# uC_ATMEL.net
KiCad netlist of a schematic drawn in EAGLE
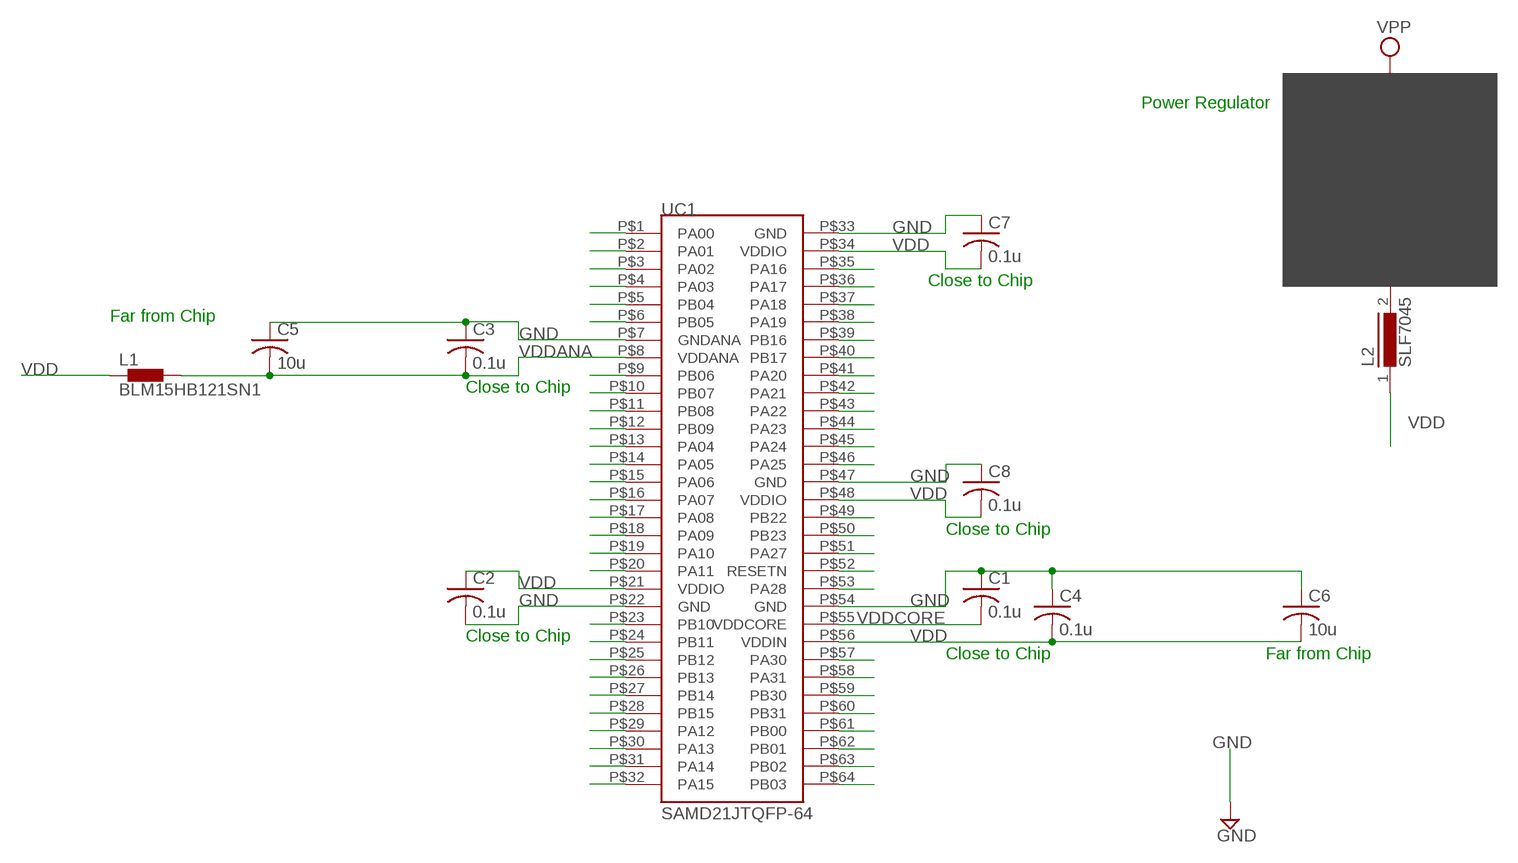
[diagram p0: schematic, sheet 1]
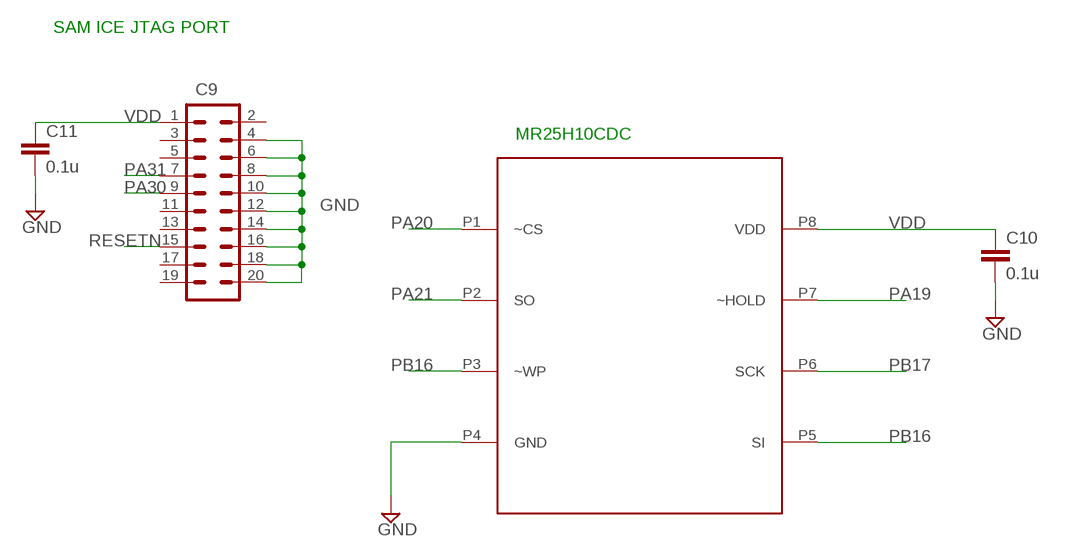
[diagram p1: schematic, sheet 2]
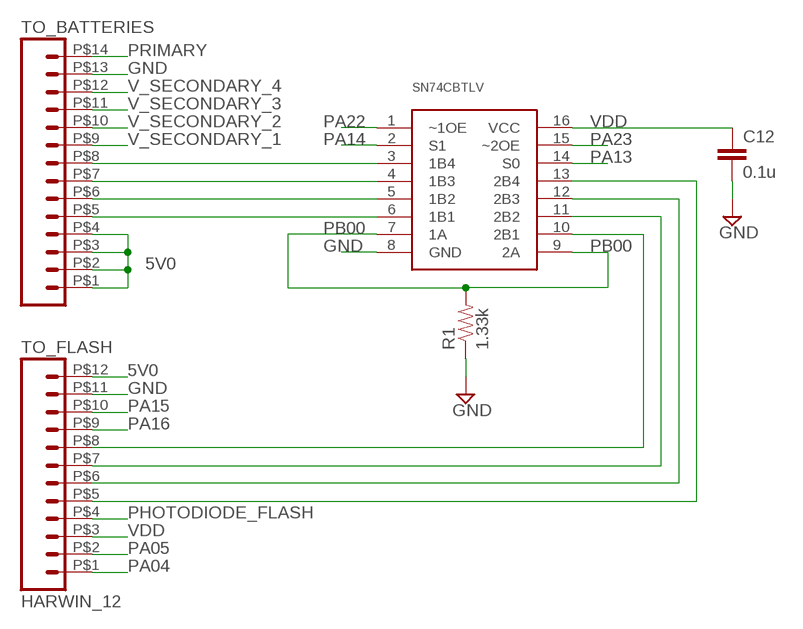
[diagram p2: schematic, sheet 3]
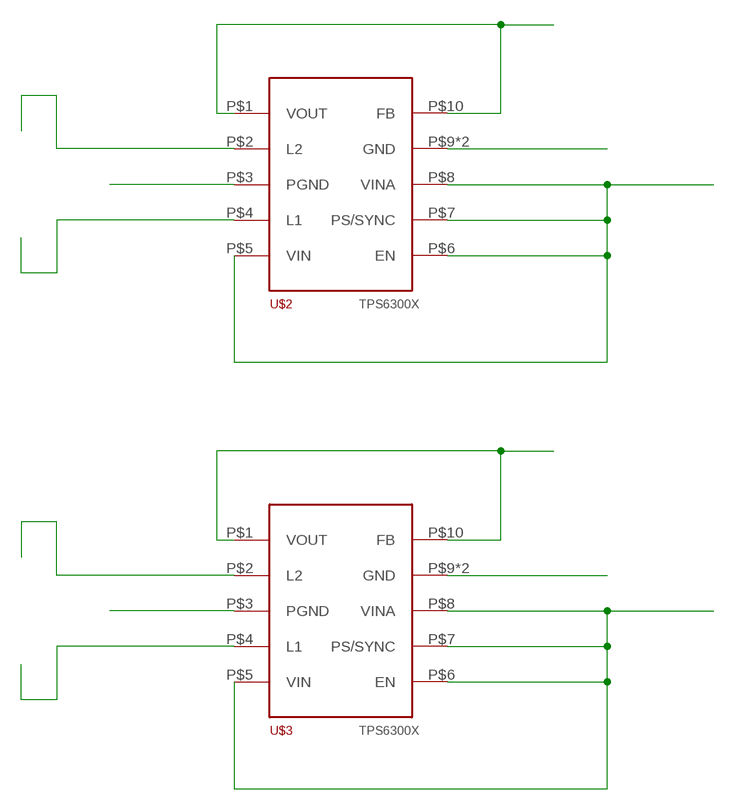
[diagram p3: schematic, sheet 4]
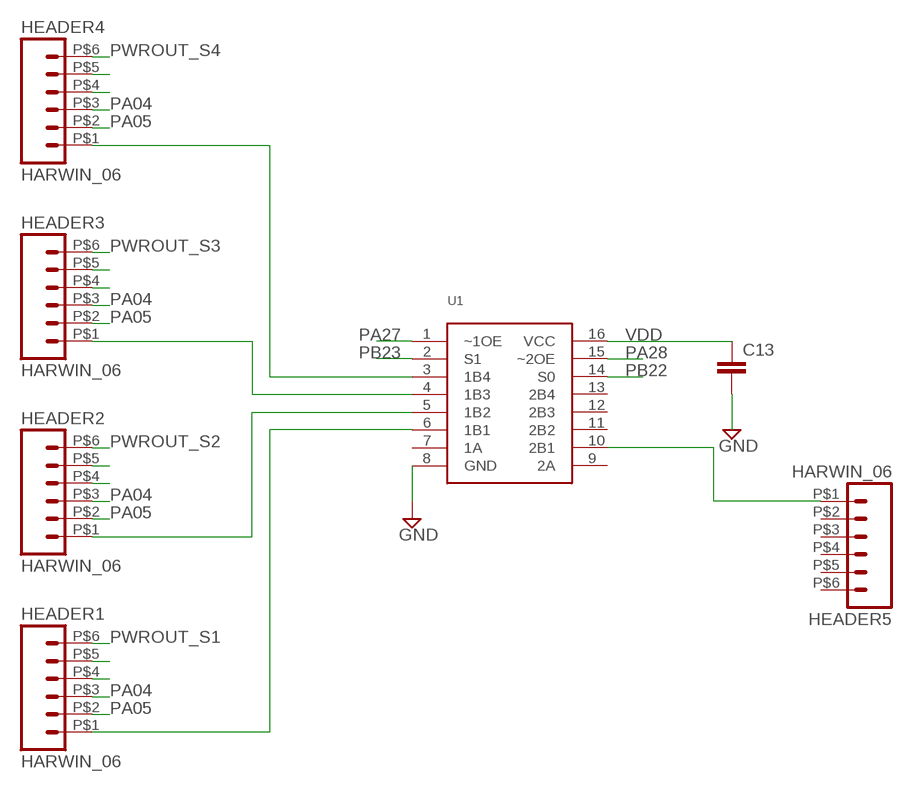
[diagram p4: schematic, sheet 5]

(export (version "E")
  (design (tool "Eeschema 10.0.6"))
  (components
    (comp (ref "C1")
      (value "0.1u")
      (footprint "eagle-import:C1812")
      (libsource (lib "eagle-import") (part "C-USC1812"))
    )
    (comp (ref "C2")
      (value "0.1u")
      (footprint "eagle-import:C1812")
      (libsource (lib "eagle-import") (part "C-USC1812"))
    )
    (comp (ref "C3")
      (value "0.1u")
      (footprint "eagle-import:C1812")
      (libsource (lib "eagle-import") (part "C-USC1812"))
    )
    (comp (ref "C4")
      (value "0.1u")
      (footprint "eagle-import:C1812")
      (libsource (lib "eagle-import") (part "C-USC1812"))
    )
    (comp (ref "C5")
      (value "10u")
      (footprint "eagle-import:C1206")
      (libsource (lib "eagle-import") (part "C-USC1206"))
    )
    (comp (ref "C6")
      (value "10u")
      (footprint "eagle-import:C1206")
      (libsource (lib "eagle-import") (part "C-USC1206"))
    )
    (comp (ref "C7")
      (value "0.1u")
      (footprint "eagle-import:C1812")
      (libsource (lib "eagle-import") (part "C-USC1812"))
    )
    (comp (ref "C8")
      (value "0.1u")
      (footprint "eagle-import:C1812")
      (libsource (lib "eagle-import") (part "C-USC1812"))
    )
    (comp (ref "L1")
      (value "BLM15HB121SN1")
      (footprint "eagle-import:0402")
      (libsource (lib "eagle-import") (part "BLM15HB121SN1"))
    )
    (comp (ref "L2")
      (value "SLF7045")
      (footprint "eagle-import:SLF7045")
      (libsource (lib "eagle-import") (part "SLF7045"))
    )
    (comp (ref "UC1")
      (value "SAMD21JTQFP-64")
      (footprint "eagle-import:TQFP-64")
      (libsource (lib "eagle-import") (part "SAMD21JTQFP-64"))
    )
    (comp (ref "C12")
      (value "0.1u")
      (footprint "eagle-import:0805")
      (libsource (lib "eagle-import") (part "CAP0805"))
    )
    (comp (ref "R1")
      (value "1.33k")
      (footprint "eagle-import:0805")
      (libsource (lib "eagle-import") (part "RESISTOR"))
    )
    (comp (ref "SN74CBTLV")
      (value "SN74CBTLV3253")
      (footprint "eagle-import:SOIC16R")
      (libsource (lib "eagle-import") (part "SN74CBTLV3253"))
    )
    (comp (ref "TO_BATTERIES")
      (value "HARWIN_14")
      (footprint "eagle-import:HARWIN_DATAMATE_14")
      (libsource (lib "eagle-import") (part "HARWIN_14"))
    )
    (comp (ref "TO_FLASH")
      (value "HARWIN_12")
      (footprint "eagle-import:HARWIN_DATAMATE_12")
      (libsource (lib "eagle-import") (part "HARWIN_12"))
    )
    (comp (ref "U$2")
      (value "TPS6300X")
      (footprint "eagle-import:QFN10_POWERPAD")
      (libsource (lib "eagle-import") (part "TPS6300X"))
    )
    (comp (ref "U$3")
      (value "TPS6300X")
      (footprint "eagle-import:QFN10_POWERPAD")
      (libsource (lib "eagle-import") (part "TPS6300X"))
    )
    (comp (ref "C9")
      (value "IDC_JTAG_CONNECTOR")
      (footprint "eagle-import:2X10")
      (libsource (lib "eagle-import") (part "IDC_JTAG_CONNECTOR"))
    )
    (comp (ref "C10")
      (value "0.1u")
      (footprint "eagle-import:0805")
      (libsource (lib "eagle-import") (part "CAP0805"))
    )
    (comp (ref "C11")
      (value "0.1u")
      (footprint "eagle-import:0805")
      (libsource (lib "eagle-import") (part "CAP0805"))
    )
    (comp (ref "U$1")
      (value "MR25H10CDC")
      (footprint "eagle-import:8PXMO-229")
      (libsource (lib "eagle-import") (part "MR25H10CDC"))
    )
    (comp (ref "C13")
      (value "CAP0805")
      (footprint "eagle-import:0805")
      (libsource (lib "eagle-import") (part "CAP0805"))
    )
    (comp (ref "HEADER1")
      (value "HARWIN_06")
      (footprint "eagle-import:HARWIN_DATAMATE_6")
      (libsource (lib "eagle-import") (part "HARWIN_06"))
    )
    (comp (ref "HEADER2")
      (value "HARWIN_06")
      (footprint "eagle-import:HARWIN_DATAMATE_6")
      (libsource (lib "eagle-import") (part "HARWIN_06"))
    )
    (comp (ref "HEADER3")
      (value "HARWIN_06")
      (footprint "eagle-import:HARWIN_DATAMATE_6")
      (libsource (lib "eagle-import") (part "HARWIN_06"))
    )
    (comp (ref "HEADER4")
      (value "HARWIN_06")
      (footprint "eagle-import:HARWIN_DATAMATE_6")
      (libsource (lib "eagle-import") (part "HARWIN_06"))
    )
    (comp (ref "HEADER5")
      (value "HARWIN_06")
      (footprint "eagle-import:HARWIN_DATAMATE_6")
      (libsource (lib "eagle-import") (part "HARWIN_06"))
    )
    (comp (ref "U1")
      (value "SN74CBTLV3253")
      (footprint "eagle-import:SOIC16R")
      (libsource (lib "eagle-import") (part "SN74CBTLV3253"))
    )
  )
  (nets
    (net (code "1") (name "5V0") (class "Default")
      (node (ref "TO_BATTERIES") (pin "P$1") (pinfunction "1_P$1") (pintype "passive"))
      (node (ref "TO_BATTERIES") (pin "P$2") (pinfunction "2_P$2") (pintype "passive"))
      (node (ref "TO_BATTERIES") (pin "P$3") (pinfunction "3_P$3") (pintype "passive"))
      (node (ref "TO_BATTERIES") (pin "P$4") (pinfunction "4_P$4") (pintype "passive"))
      (node (ref "TO_FLASH") (pin "P$12") (pinfunction "12_P$12") (pintype "passive"))
    )
    (net (code "2") (name "GND") (class "Default")
      (node (ref "C1") (pin "1") (pinfunction "1_1") (pintype "passive"))
      (node (ref "C10") (pin "2") (pinfunction "2_2") (pintype "passive"))
      (node (ref "C11") (pin "2") (pinfunction "2_2") (pintype "passive"))
      (node (ref "C12") (pin "2") (pinfunction "2_2") (pintype "passive"))
      (node (ref "C2") (pin "2") (pinfunction "2_2") (pintype "passive"))
      (node (ref "C3") (pin "1") (pinfunction "1_1") (pintype "passive"))
      (node (ref "C4") (pin "1") (pinfunction "1_1") (pintype "passive"))
      (node (ref "C5") (pin "1") (pinfunction "1_1") (pintype "passive"))
      (node (ref "C6") (pin "1") (pinfunction "1_1") (pintype "passive"))
      (node (ref "C7") (pin "1") (pinfunction "1_1") (pintype "passive"))
      (node (ref "C8") (pin "1") (pinfunction "1_1") (pintype "passive"))
      (node (ref "C9") (pin "10") (pinfunction "10_10") (pintype "passive"))
      (node (ref "C9") (pin "12") (pinfunction "12_12") (pintype "passive"))
      (node (ref "C9") (pin "14") (pinfunction "14_14") (pintype "passive"))
      (node (ref "C9") (pin "16") (pinfunction "16_16") (pintype "passive"))
      (node (ref "C9") (pin "18") (pinfunction "18_18") (pintype "passive"))
      (node (ref "C9") (pin "20") (pinfunction "20_20") (pintype "passive"))
      (node (ref "C9") (pin "4") (pinfunction "4_4") (pintype "passive"))
      (node (ref "C9") (pin "6") (pinfunction "6_6") (pintype "passive"))
      (node (ref "C9") (pin "8") (pinfunction "8_8") (pintype "passive"))
      (node (ref "R1") (pin "1") (pinfunction "1_1") (pintype "passive"))
      (node (ref "SN74CBTLV") (pin "8") (pinfunction "GND_8") (pintype "bidirectional"))
      (node (ref "TO_BATTERIES") (pin "P$13") (pinfunction "13_P$13") (pintype "passive"))
      (node (ref "TO_FLASH") (pin "P$11") (pinfunction "11_P$11") (pintype "passive"))
      (node (ref "U$1") (pin "P4") (pinfunction "GND_P4") (pintype "bidirectional"))
      (node (ref "U1") (pin "8") (pinfunction "GND_8") (pintype "bidirectional"))
      (node (ref "UC1") (pin "P$22") (pinfunction "GND_P$22") (pintype "power_in"))
      (node (ref "UC1") (pin "P$33") (pinfunction "GND_P$33") (pintype "power_in"))
      (node (ref "UC1") (pin "P$47") (pinfunction "GND_P$47") (pintype "power_in"))
      (node (ref "UC1") (pin "P$54") (pinfunction "GND_P$54") (pintype "power_in"))
      (node (ref "UC1") (pin "P$7") (pinfunction "GNDANA_P$7") (pintype "power_in"))
    )
    (net (code "3") (name "Net-(HEADER1-1)") (class "Default")
      (node (ref "HEADER1") (pin "P$1") (pinfunction "1_P$1") (pintype "passive"))
      (node (ref "U1") (pin "6") (pinfunction "1B1_6") (pintype "bidirectional"))
    )
    (net (code "4") (name "Net-(HEADER2-1)") (class "Default")
      (node (ref "HEADER2") (pin "P$1") (pinfunction "1_P$1") (pintype "passive"))
      (node (ref "U1") (pin "5") (pinfunction "1B2_5") (pintype "bidirectional"))
    )
    (net (code "5") (name "Net-(HEADER3-1)") (class "Default")
      (node (ref "HEADER3") (pin "P$1") (pinfunction "1_P$1") (pintype "passive"))
      (node (ref "U1") (pin "4") (pinfunction "1B3_4") (pintype "bidirectional"))
    )
    (net (code "6") (name "Net-(HEADER4-1)") (class "Default")
      (node (ref "HEADER4") (pin "P$1") (pinfunction "1_P$1") (pintype "passive"))
      (node (ref "U1") (pin "3") (pinfunction "1B4_3") (pintype "bidirectional"))
    )
    (net (code "7") (name "Net-(HEADER5-1)") (class "Default")
      (node (ref "HEADER5") (pin "P$1") (pinfunction "1_P$1") (pintype "passive"))
      (node (ref "U1") (pin "10") (pinfunction "2B1_10") (pintype "bidirectional"))
    )
    (net (code "8") (name "Net-(SN74CBTLV-1B1)") (class "Default")
      (node (ref "SN74CBTLV") (pin "6") (pinfunction "1B1_6") (pintype "bidirectional"))
      (node (ref "TO_BATTERIES") (pin "P$5") (pinfunction "5_P$5") (pintype "passive"))
    )
    (net (code "9") (name "Net-(SN74CBTLV-1B2)") (class "Default")
      (node (ref "SN74CBTLV") (pin "5") (pinfunction "1B2_5") (pintype "bidirectional"))
      (node (ref "TO_BATTERIES") (pin "P$6") (pinfunction "6_P$6") (pintype "passive"))
    )
    (net (code "10") (name "Net-(SN74CBTLV-1B3)") (class "Default")
      (node (ref "SN74CBTLV") (pin "4") (pinfunction "1B3_4") (pintype "bidirectional"))
      (node (ref "TO_BATTERIES") (pin "P$7") (pinfunction "7_P$7") (pintype "passive"))
    )
    (net (code "11") (name "Net-(SN74CBTLV-1B4)") (class "Default")
      (node (ref "SN74CBTLV") (pin "3") (pinfunction "1B4_3") (pintype "bidirectional"))
      (node (ref "TO_BATTERIES") (pin "P$8") (pinfunction "8_P$8") (pintype "passive"))
    )
    (net (code "12") (name "Net-(SN74CBTLV-2B1)") (class "Default")
      (node (ref "SN74CBTLV") (pin "10") (pinfunction "2B1_10") (pintype "bidirectional"))
      (node (ref "TO_FLASH") (pin "P$8") (pinfunction "8_P$8") (pintype "passive"))
    )
    (net (code "13") (name "Net-(SN74CBTLV-2B2)") (class "Default")
      (node (ref "SN74CBTLV") (pin "11") (pinfunction "2B2_11") (pintype "bidirectional"))
      (node (ref "TO_FLASH") (pin "P$7") (pinfunction "7_P$7") (pintype "passive"))
    )
    (net (code "14") (name "Net-(SN74CBTLV-2B3)") (class "Default")
      (node (ref "SN74CBTLV") (pin "12") (pinfunction "2B3_12") (pintype "bidirectional"))
      (node (ref "TO_FLASH") (pin "P$6") (pinfunction "6_P$6") (pintype "passive"))
    )
    (net (code "15") (name "Net-(SN74CBTLV-2B4)") (class "Default")
      (node (ref "SN74CBTLV") (pin "13") (pinfunction "2B4_13") (pintype "bidirectional"))
      (node (ref "TO_FLASH") (pin "P$5") (pinfunction "5_P$5") (pintype "passive"))
    )
    (net (code "16") (name "Net-(U$2-EN)") (class "Default")
      (node (ref "U$2") (pin "P$5") (pinfunction "VIN_P$5") (pintype "input"))
      (node (ref "U$2") (pin "P$6") (pinfunction "EN_P$6") (pintype "input"))
      (node (ref "U$2") (pin "P$7") (pinfunction "PS/SYNC_P$7") (pintype "input"))
      (node (ref "U$2") (pin "P$8") (pinfunction "VINA_P$8") (pintype "input"))
    )
    (net (code "17") (name "Net-(U$2-FB)") (class "Default")
      (node (ref "U$2") (pin "P$1") (pinfunction "VOUT_P$1") (pintype "output"))
      (node (ref "U$2") (pin "P$10") (pinfunction "FB_P$10") (pintype "input"))
    )
    (net (code "18") (name "Net-(U$2-GND-PadP$9)") (class "Default")
      (node (ref "U$2") (pin "P$9") (pinfunction "GND_P$9") (pintype "input"))
      (node (ref "U$2") (pin "PAD") (pinfunction "GND_PAD") (pintype "input"))
    )
    (net (code "19") (name "Net-(U$3-EN)") (class "Default")
      (node (ref "U$3") (pin "P$5") (pinfunction "VIN_P$5") (pintype "input"))
      (node (ref "U$3") (pin "P$6") (pinfunction "EN_P$6") (pintype "input"))
      (node (ref "U$3") (pin "P$7") (pinfunction "PS/SYNC_P$7") (pintype "input"))
      (node (ref "U$3") (pin "P$8") (pinfunction "VINA_P$8") (pintype "input"))
    )
    (net (code "20") (name "Net-(U$3-FB)") (class "Default")
      (node (ref "U$3") (pin "P$1") (pinfunction "VOUT_P$1") (pintype "output"))
      (node (ref "U$3") (pin "P$10") (pinfunction "FB_P$10") (pintype "input"))
    )
    (net (code "21") (name "Net-(U$3-GND-PadP$9)") (class "Default")
      (node (ref "U$3") (pin "P$9") (pinfunction "GND_P$9") (pintype "input"))
      (node (ref "U$3") (pin "PAD") (pinfunction "GND_PAD") (pintype "input"))
    )
    (net (code "22") (name "PA04") (class "Default")
      (node (ref "HEADER1") (pin "P$3") (pinfunction "3_P$3") (pintype "passive"))
      (node (ref "HEADER2") (pin "P$3") (pinfunction "3_P$3") (pintype "passive"))
      (node (ref "HEADER3") (pin "P$3") (pinfunction "3_P$3") (pintype "passive"))
      (node (ref "HEADER4") (pin "P$3") (pinfunction "3_P$3") (pintype "passive"))
      (node (ref "TO_FLASH") (pin "P$1") (pinfunction "1_P$1") (pintype "passive"))
      (node (ref "UC1") (pin "P$13") (pinfunction "PA04_P$13") (pintype "bidirectional"))
    )
    (net (code "23") (name "PA05") (class "Default")
      (node (ref "HEADER1") (pin "P$2") (pinfunction "2_P$2") (pintype "passive"))
      (node (ref "HEADER2") (pin "P$2") (pinfunction "2_P$2") (pintype "passive"))
      (node (ref "HEADER3") (pin "P$2") (pinfunction "2_P$2") (pintype "passive"))
      (node (ref "HEADER4") (pin "P$2") (pinfunction "2_P$2") (pintype "passive"))
      (node (ref "TO_FLASH") (pin "P$2") (pinfunction "2_P$2") (pintype "passive"))
      (node (ref "UC1") (pin "P$14") (pinfunction "PA05_P$14") (pintype "bidirectional"))
    )
    (net (code "24") (name "PA13") (class "Default")
      (node (ref "SN74CBTLV") (pin "14") (pinfunction "S0_14") (pintype "bidirectional"))
      (node (ref "UC1") (pin "P$30") (pinfunction "PA13_P$30") (pintype "bidirectional"))
    )
    (net (code "25") (name "PA14") (class "Default")
      (node (ref "SN74CBTLV") (pin "2") (pinfunction "S1_2") (pintype "bidirectional"))
      (node (ref "UC1") (pin "P$31") (pinfunction "PA14_P$31") (pintype "bidirectional"))
    )
    (net (code "26") (name "PA15") (class "Default")
      (node (ref "TO_FLASH") (pin "P$10") (pinfunction "10_P$10") (pintype "passive"))
      (node (ref "UC1") (pin "P$32") (pinfunction "PA15_P$32") (pintype "bidirectional"))
    )
    (net (code "27") (name "PA16") (class "Default")
      (node (ref "TO_FLASH") (pin "P$9") (pinfunction "9_P$9") (pintype "passive"))
      (node (ref "UC1") (pin "P$35") (pinfunction "PA16_P$35") (pintype "bidirectional"))
    )
    (net (code "28") (name "PA19") (class "Default")
      (node (ref "U$1") (pin "P7") (pinfunction "~{HOLD}_P7") (pintype "bidirectional"))
      (node (ref "UC1") (pin "P$38") (pinfunction "PA19_P$38") (pintype "bidirectional"))
    )
    (net (code "29") (name "PA20") (class "Default")
      (node (ref "U$1") (pin "P1") (pinfunction "~{CS}_P1") (pintype "bidirectional"))
      (node (ref "UC1") (pin "P$41") (pinfunction "PA20_P$41") (pintype "bidirectional"))
    )
    (net (code "30") (name "PA21") (class "Default")
      (node (ref "U$1") (pin "P2") (pinfunction "SO_P2") (pintype "bidirectional"))
      (node (ref "UC1") (pin "P$42") (pinfunction "PA21_P$42") (pintype "bidirectional"))
    )
    (net (code "31") (name "PA22") (class "Default")
      (node (ref "SN74CBTLV") (pin "1") (pinfunction "~{1OE}_1") (pintype "bidirectional"))
      (node (ref "UC1") (pin "P$43") (pinfunction "PA22_P$43") (pintype "bidirectional"))
    )
    (net (code "32") (name "PA23") (class "Default")
      (node (ref "SN74CBTLV") (pin "15") (pinfunction "~{2OE}_15") (pintype "bidirectional"))
      (node (ref "UC1") (pin "P$44") (pinfunction "PA23_P$44") (pintype "bidirectional"))
    )
    (net (code "33") (name "PA27") (class "Default")
      (node (ref "U1") (pin "1") (pinfunction "~{1OE}_1") (pintype "bidirectional"))
      (node (ref "UC1") (pin "P$51") (pinfunction "PA27_P$51") (pintype "bidirectional"))
    )
    (net (code "34") (name "PA28") (class "Default")
      (node (ref "U1") (pin "15") (pinfunction "~{2OE}_15") (pintype "bidirectional"))
      (node (ref "UC1") (pin "P$53") (pinfunction "PA28_P$53") (pintype "bidirectional"))
    )
    (net (code "35") (name "PA30") (class "Default")
      (node (ref "C9") (pin "9") (pinfunction "9_9") (pintype "passive"))
      (node (ref "UC1") (pin "P$57") (pinfunction "PA30_P$57") (pintype "bidirectional"))
    )
    (net (code "36") (name "PA31") (class "Default")
      (node (ref "C9") (pin "7") (pinfunction "7_7") (pintype "passive"))
      (node (ref "UC1") (pin "P$58") (pinfunction "PA31_P$58") (pintype "bidirectional"))
    )
    (net (code "37") (name "PB00") (class "Default")
      (node (ref "R1") (pin "2") (pinfunction "2_2") (pintype "passive"))
      (node (ref "SN74CBTLV") (pin "7") (pinfunction "1A_7") (pintype "bidirectional"))
      (node (ref "SN74CBTLV") (pin "9") (pinfunction "2A_9") (pintype "bidirectional"))
      (node (ref "UC1") (pin "P$61") (pinfunction "PB00_P$61") (pintype "bidirectional"))
    )
    (net (code "38") (name "PB16") (class "Default")
      (node (ref "U$1") (pin "P3") (pinfunction "~{WP}_P3") (pintype "bidirectional"))
      (node (ref "U$1") (pin "P5") (pinfunction "SI_P5") (pintype "bidirectional"))
      (node (ref "UC1") (pin "P$39") (pinfunction "PB16_P$39") (pintype "bidirectional"))
    )
    (net (code "39") (name "PB17") (class "Default")
      (node (ref "U$1") (pin "P6") (pinfunction "SCK_P6") (pintype "bidirectional"))
      (node (ref "UC1") (pin "P$40") (pinfunction "PB17_P$40") (pintype "bidirectional"))
    )
    (net (code "40") (name "PB22") (class "Default")
      (node (ref "U1") (pin "14") (pinfunction "S0_14") (pintype "bidirectional"))
      (node (ref "UC1") (pin "P$49") (pinfunction "PB22_P$49") (pintype "bidirectional"))
    )
    (net (code "41") (name "PB23") (class "Default")
      (node (ref "U1") (pin "2") (pinfunction "S1_2") (pintype "bidirectional"))
      (node (ref "UC1") (pin "P$50") (pinfunction "PB23_P$50") (pintype "bidirectional"))
    )
    (net (code "42") (name "PHOTODIODE_FLASH") (class "Default")
      (node (ref "TO_FLASH") (pin "P$4") (pinfunction "4_P$4") (pintype "passive"))
    )
    (net (code "43") (name "PRIMARY") (class "Default")
      (node (ref "TO_BATTERIES") (pin "P$14") (pinfunction "14_P$14") (pintype "passive"))
    )
    (net (code "44") (name "PWROUT_S1") (class "Default")
      (node (ref "HEADER1") (pin "P$6") (pinfunction "6_P$6") (pintype "passive"))
    )
    (net (code "45") (name "PWROUT_S2") (class "Default")
      (node (ref "HEADER2") (pin "P$6") (pinfunction "6_P$6") (pintype "passive"))
    )
    (net (code "46") (name "PWROUT_S3") (class "Default")
      (node (ref "HEADER3") (pin "P$6") (pinfunction "6_P$6") (pintype "passive"))
    )
    (net (code "47") (name "PWROUT_S4") (class "Default")
      (node (ref "HEADER4") (pin "P$6") (pinfunction "6_P$6") (pintype "passive"))
    )
    (net (code "48") (name "RESETN") (class "Default")
      (node (ref "C9") (pin "15") (pinfunction "15_15") (pintype "passive"))
      (node (ref "UC1") (pin "P$52") (pinfunction "RESETN_P$52") (pintype "input"))
    )
    (net (code "49") (name "VDD") (class "Default")
      (node (ref "C10") (pin "1") (pinfunction "1_1") (pintype "passive"))
      (node (ref "C11") (pin "1") (pinfunction "1_1") (pintype "passive"))
      (node (ref "C12") (pin "1") (pinfunction "1_1") (pintype "passive"))
      (node (ref "C13") (pin "1") (pinfunction "1_1") (pintype "passive"))
      (node (ref "C2") (pin "1") (pinfunction "1_1") (pintype "passive"))
      (node (ref "C4") (pin "2") (pinfunction "2_2") (pintype "passive"))
      (node (ref "C6") (pin "2") (pinfunction "2_2") (pintype "passive"))
      (node (ref "C7") (pin "2") (pinfunction "2_2") (pintype "passive"))
      (node (ref "C8") (pin "2") (pinfunction "2_2") (pintype "passive"))
      (node (ref "C9") (pin "1") (pinfunction "1_1") (pintype "passive"))
      (node (ref "L1") (pin "1") (pinfunction "1_1") (pintype "passive"))
      (node (ref "L2") (pin "1") (pinfunction "1_1") (pintype "passive"))
      (node (ref "SN74CBTLV") (pin "16") (pinfunction "VCC_16") (pintype "bidirectional"))
      (node (ref "TO_FLASH") (pin "P$3") (pinfunction "3_P$3") (pintype "passive"))
      (node (ref "U$1") (pin "P8") (pinfunction "VDD_P8") (pintype "bidirectional"))
      (node (ref "U1") (pin "16") (pinfunction "VCC_16") (pintype "bidirectional"))
      (node (ref "UC1") (pin "P$21") (pinfunction "VDDIO_P$21") (pintype "power_in"))
      (node (ref "UC1") (pin "P$34") (pinfunction "VDDIO_P$34") (pintype "power_in"))
      (node (ref "UC1") (pin "P$48") (pinfunction "VDDIO_P$48") (pintype "power_in"))
      (node (ref "UC1") (pin "P$56") (pinfunction "VDDIN_P$56") (pintype "power_in"))
    )
    (net (code "50") (name "VDDANA") (class "Default")
      (node (ref "C3") (pin "2") (pinfunction "2_2") (pintype "passive"))
      (node (ref "C5") (pin "2") (pinfunction "2_2") (pintype "passive"))
      (node (ref "L1") (pin "2") (pinfunction "2_2") (pintype "passive"))
      (node (ref "UC1") (pin "P$8") (pinfunction "VDDANA_P$8") (pintype "power_in"))
    )
    (net (code "51") (name "VDDCORE") (class "Default")
      (node (ref "C1") (pin "2") (pinfunction "2_2") (pintype "passive"))
      (node (ref "UC1") (pin "P$55") (pinfunction "VDDCORE_P$55") (pintype "power_in"))
    )
    (net (code "53") (name "V_SECONDARY_1") (class "Default")
      (node (ref "TO_BATTERIES") (pin "P$9") (pinfunction "9_P$9") (pintype "passive"))
    )
    (net (code "54") (name "V_SECONDARY_2") (class "Default")
      (node (ref "TO_BATTERIES") (pin "P$10") (pinfunction "10_P$10") (pintype "passive"))
    )
    (net (code "55") (name "V_SECONDARY_3") (class "Default")
      (node (ref "TO_BATTERIES") (pin "P$11") (pinfunction "11_P$11") (pintype "passive"))
    )
    (net (code "56") (name "V_SECONDARY_4") (class "Default")
      (node (ref "TO_BATTERIES") (pin "P$12") (pinfunction "12_P$12") (pintype "passive"))
    )
    (net (code "57") (name "unconnected-(C9-Pad2)") (class "Default")
      (node (ref "C9") (pin "2") (pinfunction "2_2") (pintype "passive"))
    )
    (net (code "58") (name "unconnected-(C9-Pad3)") (class "Default")
      (node (ref "C9") (pin "3") (pinfunction "3_3") (pintype "passive"))
    )
    (net (code "59") (name "unconnected-(C9-Pad5)") (class "Default")
      (node (ref "C9") (pin "5") (pinfunction "5_5") (pintype "passive"))
    )
    (net (code "60") (name "unconnected-(C9-Pad11)") (class "Default")
      (node (ref "C9") (pin "11") (pinfunction "11_11") (pintype "passive"))
    )
    (net (code "61") (name "unconnected-(C9-Pad13)") (class "Default")
      (node (ref "C9") (pin "13") (pinfunction "13_13") (pintype "passive"))
    )
    (net (code "62") (name "unconnected-(C9-Pad17)") (class "Default")
      (node (ref "C9") (pin "17") (pinfunction "17_17") (pintype "passive"))
    )
    (net (code "63") (name "unconnected-(C9-Pad19)") (class "Default")
      (node (ref "C9") (pin "19") (pinfunction "19_19") (pintype "passive"))
    )
    (net (code "64") (name "unconnected-(C13-Pad2)") (class "Default")
      (node (ref "C13") (pin "2") (pinfunction "2_2") (pintype "passive"))
    )
    (net (code "65") (name "unconnected-(HEADER1-4-PadP$4)") (class "Default")
      (node (ref "HEADER1") (pin "P$4") (pinfunction "4_P$4") (pintype "passive"))
    )
    (net (code "66") (name "unconnected-(HEADER1-5-PadP$5)") (class "Default")
      (node (ref "HEADER1") (pin "P$5") (pinfunction "5_P$5") (pintype "passive"))
    )
    (net (code "67") (name "unconnected-(HEADER2-4-PadP$4)") (class "Default")
      (node (ref "HEADER2") (pin "P$4") (pinfunction "4_P$4") (pintype "passive"))
    )
    (net (code "68") (name "unconnected-(HEADER2-5-PadP$5)") (class "Default")
      (node (ref "HEADER2") (pin "P$5") (pinfunction "5_P$5") (pintype "passive"))
    )
    (net (code "69") (name "unconnected-(HEADER3-4-PadP$4)") (class "Default")
      (node (ref "HEADER3") (pin "P$4") (pinfunction "4_P$4") (pintype "passive"))
    )
    (net (code "70") (name "unconnected-(HEADER3-5-PadP$5)") (class "Default")
      (node (ref "HEADER3") (pin "P$5") (pinfunction "5_P$5") (pintype "passive"))
    )
    (net (code "71") (name "unconnected-(HEADER4-4-PadP$4)") (class "Default")
      (node (ref "HEADER4") (pin "P$4") (pinfunction "4_P$4") (pintype "passive"))
    )
    (net (code "72") (name "unconnected-(HEADER4-5-PadP$5)") (class "Default")
      (node (ref "HEADER4") (pin "P$5") (pinfunction "5_P$5") (pintype "passive"))
    )
    (net (code "73") (name "unconnected-(HEADER5-2-PadP$2)") (class "Default")
      (node (ref "HEADER5") (pin "P$2") (pinfunction "2_P$2") (pintype "passive"))
    )
    (net (code "74") (name "unconnected-(HEADER5-3-PadP$3)") (class "Default")
      (node (ref "HEADER5") (pin "P$3") (pinfunction "3_P$3") (pintype "passive"))
    )
    (net (code "75") (name "unconnected-(HEADER5-4-PadP$4)") (class "Default")
      (node (ref "HEADER5") (pin "P$4") (pinfunction "4_P$4") (pintype "passive"))
    )
    (net (code "76") (name "unconnected-(HEADER5-5-PadP$5)") (class "Default")
      (node (ref "HEADER5") (pin "P$5") (pinfunction "5_P$5") (pintype "passive"))
    )
    (net (code "77") (name "unconnected-(HEADER5-6-PadP$6)") (class "Default")
      (node (ref "HEADER5") (pin "P$6") (pinfunction "6_P$6") (pintype "passive"))
    )
    (net (code "78") (name "unconnected-(L2-Pad2)") (class "Default")
      (node (ref "L2") (pin "2") (pinfunction "2_2") (pintype "passive"))
    )
    (net (code "79") (name "unconnected-(U$2-L1-PadP$4)") (class "Default")
      (node (ref "U$2") (pin "P$4") (pinfunction "L1_P$4") (pintype "input"))
    )
    (net (code "80") (name "unconnected-(U$2-L2-PadP$2)") (class "Default")
      (node (ref "U$2") (pin "P$2") (pinfunction "L2_P$2") (pintype "input"))
    )
    (net (code "81") (name "unconnected-(U$2-PGND-PadP$3)") (class "Default")
      (node (ref "U$2") (pin "P$3") (pinfunction "PGND_P$3") (pintype "input"))
    )
    (net (code "82") (name "unconnected-(U$3-L1-PadP$4)") (class "Default")
      (node (ref "U$3") (pin "P$4") (pinfunction "L1_P$4") (pintype "input"))
    )
    (net (code "83") (name "unconnected-(U$3-L2-PadP$2)") (class "Default")
      (node (ref "U$3") (pin "P$2") (pinfunction "L2_P$2") (pintype "input"))
    )
    (net (code "84") (name "unconnected-(U$3-PGND-PadP$3)") (class "Default")
      (node (ref "U$3") (pin "P$3") (pinfunction "PGND_P$3") (pintype "input"))
    )
    (net (code "85") (name "unconnected-(U1-1A-Pad7)") (class "Default")
      (node (ref "U1") (pin "7") (pinfunction "1A_7") (pintype "bidirectional"))
    )
    (net (code "86") (name "unconnected-(U1-2A-Pad9)") (class "Default")
      (node (ref "U1") (pin "9") (pinfunction "2A_9") (pintype "bidirectional"))
    )
    (net (code "87") (name "unconnected-(U1-2B2-Pad11)") (class "Default")
      (node (ref "U1") (pin "11") (pinfunction "2B2_11") (pintype "bidirectional"))
    )
    (net (code "88") (name "unconnected-(U1-2B3-Pad12)") (class "Default")
      (node (ref "U1") (pin "12") (pinfunction "2B3_12") (pintype "bidirectional"))
    )
    (net (code "89") (name "unconnected-(U1-2B4-Pad13)") (class "Default")
      (node (ref "U1") (pin "13") (pinfunction "2B4_13") (pintype "bidirectional"))
    )
    (net (code "90") (name "unconnected-(UC1-PA00-PadP$1)") (class "Default")
      (node (ref "UC1") (pin "P$1") (pinfunction "PA00_P$1") (pintype "bidirectional"))
    )
    (net (code "91") (name "unconnected-(UC1-PA01-PadP$2)") (class "Default")
      (node (ref "UC1") (pin "P$2") (pinfunction "PA01_P$2") (pintype "bidirectional"))
    )
    (net (code "92") (name "unconnected-(UC1-PA02-PadP$3)") (class "Default")
      (node (ref "UC1") (pin "P$3") (pinfunction "PA02_P$3") (pintype "bidirectional"))
    )
    (net (code "93") (name "unconnected-(UC1-PA03-PadP$4)") (class "Default")
      (node (ref "UC1") (pin "P$4") (pinfunction "PA03_P$4") (pintype "bidirectional"))
    )
    (net (code "94") (name "unconnected-(UC1-PA06-PadP$15)") (class "Default")
      (node (ref "UC1") (pin "P$15") (pinfunction "PA06_P$15") (pintype "bidirectional"))
    )
    (net (code "95") (name "unconnected-(UC1-PA07-PadP$16)") (class "Default")
      (node (ref "UC1") (pin "P$16") (pinfunction "PA07_P$16") (pintype "bidirectional"))
    )
    (net (code "96") (name "unconnected-(UC1-PA08-PadP$17)") (class "Default")
      (node (ref "UC1") (pin "P$17") (pinfunction "PA08_P$17") (pintype "bidirectional"))
    )
    (net (code "97") (name "unconnected-(UC1-PA09-PadP$18)") (class "Default")
      (node (ref "UC1") (pin "P$18") (pinfunction "PA09_P$18") (pintype "bidirectional"))
    )
    (net (code "98") (name "unconnected-(UC1-PA10-PadP$19)") (class "Default")
      (node (ref "UC1") (pin "P$19") (pinfunction "PA10_P$19") (pintype "bidirectional"))
    )
    (net (code "99") (name "unconnected-(UC1-PA11-PadP$20)") (class "Default")
      (node (ref "UC1") (pin "P$20") (pinfunction "PA11_P$20") (pintype "bidirectional"))
    )
    (net (code "100") (name "unconnected-(UC1-PA12-PadP$29)") (class "Default")
      (node (ref "UC1") (pin "P$29") (pinfunction "PA12_P$29") (pintype "bidirectional"))
    )
    (net (code "101") (name "unconnected-(UC1-PA17-PadP$36)") (class "Default")
      (node (ref "UC1") (pin "P$36") (pinfunction "PA17_P$36") (pintype "bidirectional"))
    )
    (net (code "102") (name "unconnected-(UC1-PA18-PadP$37)") (class "Default")
      (node (ref "UC1") (pin "P$37") (pinfunction "PA18_P$37") (pintype "bidirectional"))
    )
    (net (code "103") (name "unconnected-(UC1-PA24-PadP$45)") (class "Default")
      (node (ref "UC1") (pin "P$45") (pinfunction "PA24_P$45") (pintype "bidirectional"))
    )
    (net (code "104") (name "unconnected-(UC1-PA25-PadP$46)") (class "Default")
      (node (ref "UC1") (pin "P$46") (pinfunction "PA25_P$46") (pintype "bidirectional"))
    )
    (net (code "105") (name "unconnected-(UC1-PB01-PadP$62)") (class "Default")
      (node (ref "UC1") (pin "P$62") (pinfunction "PB01_P$62") (pintype "bidirectional"))
    )
    (net (code "106") (name "unconnected-(UC1-PB02-PadP$63)") (class "Default")
      (node (ref "UC1") (pin "P$63") (pinfunction "PB02_P$63") (pintype "bidirectional"))
    )
    (net (code "107") (name "unconnected-(UC1-PB03-PadP$64)") (class "Default")
      (node (ref "UC1") (pin "P$64") (pinfunction "PB03_P$64") (pintype "bidirectional"))
    )
    (net (code "108") (name "unconnected-(UC1-PB04-PadP$5)") (class "Default")
      (node (ref "UC1") (pin "P$5") (pinfunction "PB04_P$5") (pintype "bidirectional"))
    )
    (net (code "109") (name "unconnected-(UC1-PB05-PadP$6)") (class "Default")
      (node (ref "UC1") (pin "P$6") (pinfunction "PB05_P$6") (pintype "bidirectional"))
    )
    (net (code "110") (name "unconnected-(UC1-PB06-PadP$9)") (class "Default")
      (node (ref "UC1") (pin "P$9") (pinfunction "PB06_P$9") (pintype "bidirectional"))
    )
    (net (code "111") (name "unconnected-(UC1-PB07-PadP$10)") (class "Default")
      (node (ref "UC1") (pin "P$10") (pinfunction "PB07_P$10") (pintype "bidirectional"))
    )
    (net (code "112") (name "unconnected-(UC1-PB08-PadP$11)") (class "Default")
      (node (ref "UC1") (pin "P$11") (pinfunction "PB08_P$11") (pintype "bidirectional"))
    )
    (net (code "113") (name "unconnected-(UC1-PB09-PadP$12)") (class "Default")
      (node (ref "UC1") (pin "P$12") (pinfunction "PB09_P$12") (pintype "bidirectional"))
    )
    (net (code "114") (name "unconnected-(UC1-PB10-PadP$23)") (class "Default")
      (node (ref "UC1") (pin "P$23") (pinfunction "PB10_P$23") (pintype "bidirectional"))
    )
    (net (code "115") (name "unconnected-(UC1-PB11-PadP$24)") (class "Default")
      (node (ref "UC1") (pin "P$24") (pinfunction "PB11_P$24") (pintype "bidirectional"))
    )
    (net (code "116") (name "unconnected-(UC1-PB12-PadP$25)") (class "Default")
      (node (ref "UC1") (pin "P$25") (pinfunction "PB12_P$25") (pintype "bidirectional"))
    )
    (net (code "117") (name "unconnected-(UC1-PB13-PadP$26)") (class "Default")
      (node (ref "UC1") (pin "P$26") (pinfunction "PB13_P$26") (pintype "bidirectional"))
    )
    (net (code "118") (name "unconnected-(UC1-PB14-PadP$27)") (class "Default")
      (node (ref "UC1") (pin "P$27") (pinfunction "PB14_P$27") (pintype "bidirectional"))
    )
    (net (code "119") (name "unconnected-(UC1-PB15-PadP$28)") (class "Default")
      (node (ref "UC1") (pin "P$28") (pinfunction "PB15_P$28") (pintype "bidirectional"))
    )
    (net (code "120") (name "unconnected-(UC1-PB30-PadP$59)") (class "Default")
      (node (ref "UC1") (pin "P$59") (pinfunction "PB30_P$59") (pintype "bidirectional"))
    )
    (net (code "121") (name "unconnected-(UC1-PB31-PadP$60)") (class "Default")
      (node (ref "UC1") (pin "P$60") (pinfunction "PB31_P$60") (pintype "bidirectional"))
    )
  )
)
